# FPGA_Config.net
KiCad netlist of a schematic drawn in Altium Designer
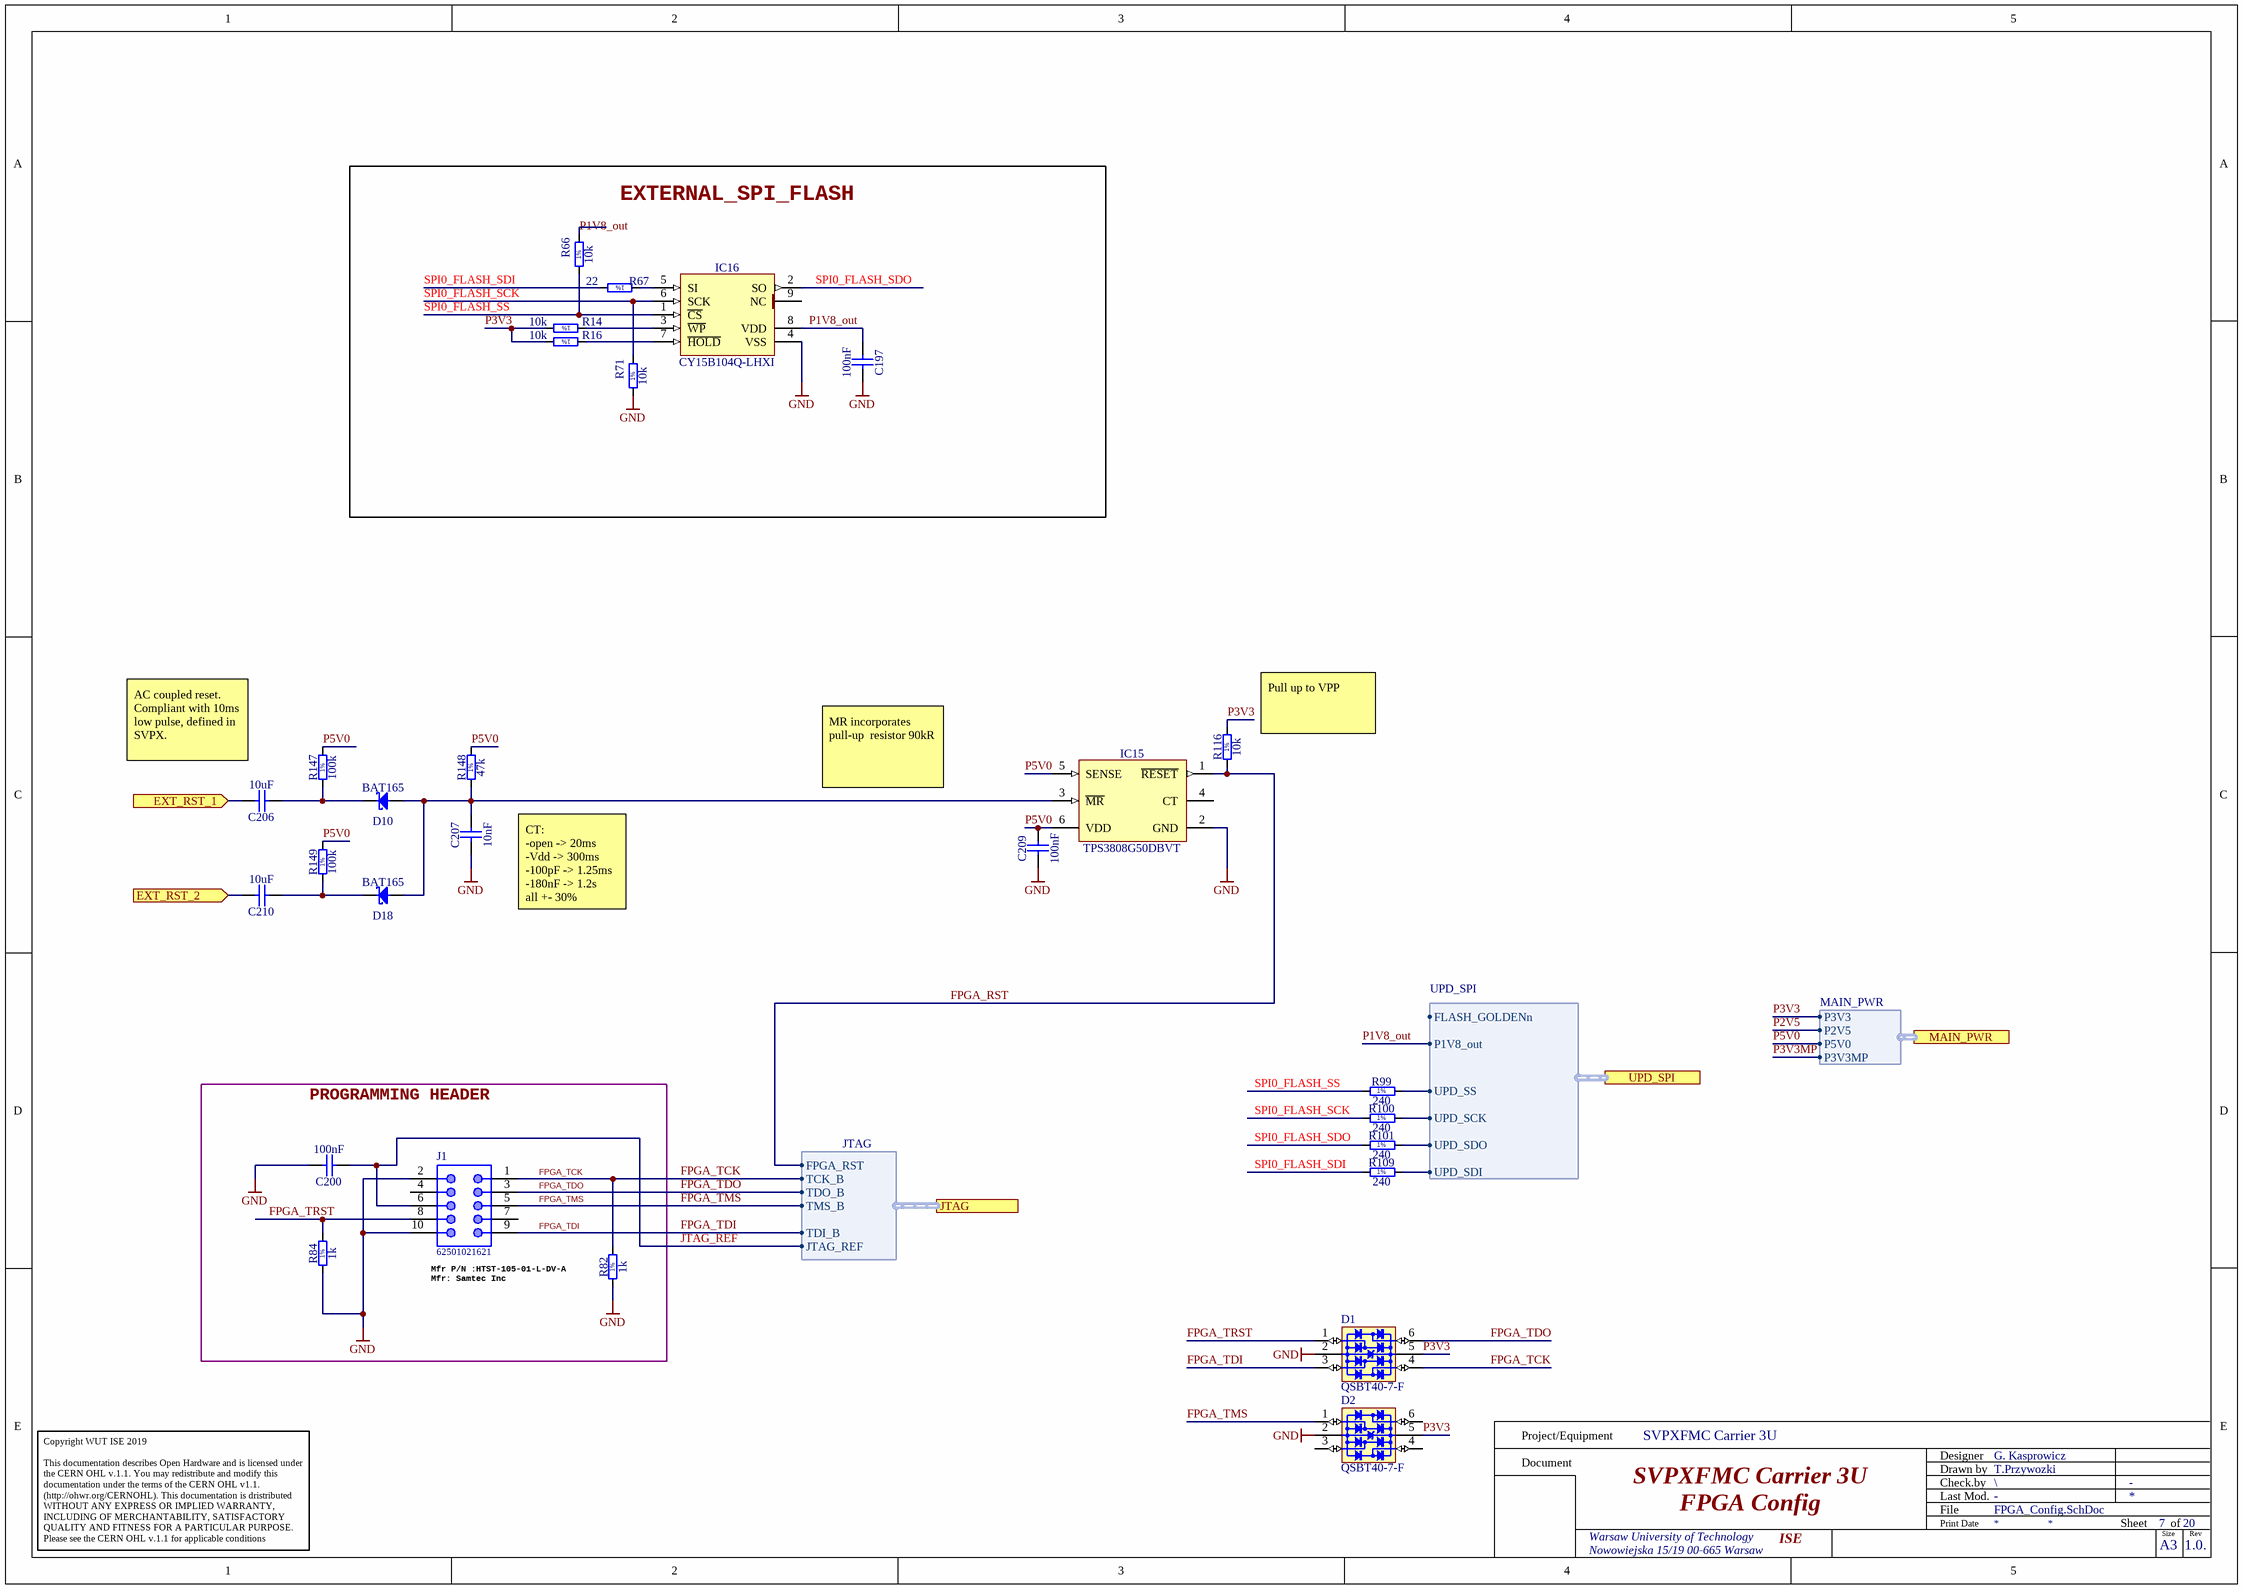
[diagram p0: FPGA_Config.SchDoc]

(export (version "E")
  (design (tool "Eeschema 10.0.6"))
  (components
    (comp (ref "C197")
      (value "100nF")
      (footprint "CAPC0603X33N")
      (description "Non-polarised capacitor")
      (fields
        (field (name "PART NUMBER") "CC0201_100NF_6.3V_10%_X5R")
        (field (name "MANUFACTURER") "GENERIC")
        (field (name "AUTHOR") "CERN DEM JLC")
      )
      (libsource (lib "Capacitors") (part "Capacitor - non polarized"))
    )
    (comp (ref "C200")
      (value "100nF")
      (footprint "CAPC0603X33N")
      (description "Non-polarised capacitor")
      (fields
        (field (name "MANUFACTURER") "GENERIC")
        (field (name "PART NUMBER") "CC0201_100NF_6.3V_10%_X5R")
        (field (name "AUTHOR") "CERN DEM JLC")
      )
      (libsource (lib "Capacitors") (part "Capacitor - non polarized"))
    )
    (comp (ref "C206")
      (value "10uF")
      (footprint "CAPC1608X80N")
      (description "Non-polarised capacitor")
      (fields
        (field (name "PART NUMBER") "CC0603_10UF_16V_20%_X5R")
        (field (name "VOLTAGE") "16V")
        (field (name "AUTHOR") "CERN DEM MR")
      )
      (libsource (lib "Capacitors") (part "Capacitor - non polarized"))
    )
    (comp (ref "C207")
      (value "10nF")
      (footprint "CAPC1005X55N")
      (description "Non-polarised capacitor")
      (fields
        (field (name "PART NUMBER") "CC0402_10NF_50V_10%_X7R")
        (field (name "VOLTAGE") "50V")
        (field (name "AUTHOR") "CERN DEM MR")
      )
      (libsource (lib "Capacitors") (part "Capacitor - non polarized"))
    )
    (comp (ref "C209")
      (value "100nF")
      (footprint "CAPC1005X55N")
      (description "Non-polarised capacitor")
      (fields
        (field (name "PART NUMBER") "CC0402_100NF_25V_10%_X7R_YUDEN_TMK105B7104KVHF")
        (field (name "VOLTAGE") "25V")
        (field (name "AUTHOR") "CERN DEM JLC")
      )
      (libsource (lib "Capacitors") (part "Capacitor - non polarized"))
    )
    (comp (ref "C210")
      (value "10uF")
      (footprint "CAPC1608X80N")
      (description "Non-polarised capacitor")
      (fields
        (field (name "PART NUMBER") "CC0603_10UF_16V_20%_X5R")
        (field (name "VOLTAGE") "16V")
        (field (name "AUTHOR") "CERN DEM MR")
      )
      (libsource (lib "Capacitors") (part "Capacitor - non polarized"))
    )
    (comp (ref "D1")
      (value "QSBT40-7-F")
      (footprint "SOT65P210X110-6N")
      (libsource (lib "LIBRARY_SCH") (part "D_TVS_QSBT40-7-F"))
    )
    (comp (ref "D2")
      (value "QSBT40-7-F")
      (footprint "SOT65P210X110-6N")
      (libsource (lib "LIBRARY_SCH") (part "D_TVS_QSBT40-7-F"))
    )
    (comp (ref "D10")
      (value "BAT165")
      (footprint "SOD2512X110N")
      (description "Schottky Diode")
      (fields
        (field (name "VOLTAGE") "40V")
        (field (name "POWER") "750mA")
        (field (name "AUTHOR") "CERN DEM JLC")
      )
      (libsource (lib "ICs And Semiconductors") (part "Diode Schottky"))
    )
    (comp (ref "D18")
      (value "BAT165")
      (footprint "SOD2512X110N")
      (description "Schottky Diode")
      (fields
        (field (name "VOLTAGE") "40V")
        (field (name "POWER") "750mA")
        (field (name "AUTHOR") "CERN DEM JLC")
      )
      (libsource (lib "ICs And Semiconductors") (part "Diode Schottky"))
    )
    (comp (ref "IC15")
      (value "TPS3808G50DBVT")
      (footprint "SOT95P280X145-6N")
      (description "Low Quiescent Current, Programmable-Delay Supervisory Circuit")
      (fields (field (name "MANUFACTURER") "TEXAS INSTRUMENTS") (field (name "AUTHOR") "CERN DEM JLC"))
      (libsource (lib "ICs And Semiconductors") (part "TPS3808xxxDBV"))
    )
    (comp (ref "IC16")
      (value "CY15B104Q-LHXI")
      (footprint "SON127P600X500X80-9N-R240X410")
      (description "4Mb Serial 3V F-RAM Memory")
      (fields (field (name "MANUFACTURER") "CYPRESS") (field (name "AUTHOR") "CERN DEM MR"))
      (libsource (lib "ICs And Semiconductors") (part "CY15B104Q"))
    )
    (comp (ref "J1")
      (value "62501021621")
      (footprint "62501021621")
      (description "Male Box Header WR-BHD with long lever, THT, Vertical, pitch 2.00 mm, 10 pins")
      (fields (field (name "PUBLISHER") "Wurth Elektronik"))
      (libsource (lib "ALTIUM-WR-BHD_BOX_HEADER_200MM_MALE-rev18b") (part "62501021621"))
    )
    (comp (ref "R14")
      (value "10k")
      (footprint "RESC1005X40N")
      (description "Resistor - 1%")
      (fields
        (field (name "MANUFACTURER PART NUMBER") "R0402_10K_1%_0.0625W_100PPM")
        (field (name "MANUFACTURER") "GENERIC")
        (field (name "AUTHOR") "CERN DEM JLC")
      )
      (libsource (lib "Resistors") (part "Resistor - 1%"))
    )
    (comp (ref "R16")
      (value "10k")
      (footprint "RESC1005X40N")
      (description "Resistor - 1%")
      (fields
        (field (name "MANUFACTURER PART NUMBER") "R0402_10K_1%_0.0625W_100PPM")
        (field (name "MANUFACTURER") "GENERIC")
        (field (name "AUTHOR") "CERN DEM JLC")
      )
      (libsource (lib "Resistors") (part "Resistor - 1%"))
    )
    (comp (ref "R66")
      (value "10k")
      (footprint "RESC1005X40N")
      (description "Resistor - 1%")
      (fields
        (field (name "MANUFACTURER PART NUMBER") "R0402_10K_1%_0.0625W_100PPM")
        (field (name "MANUFACTURER") "GENERIC")
        (field (name "AUTHOR") "CERN DEM JLC")
      )
      (libsource (lib "Resistors") (part "Resistor - 1%"))
    )
    (comp (ref "R67")
      (value "22")
      (footprint "RESC1005X40N")
      (description "Resistor - 1%")
      (fields
        (field (name "PART NUMBER") "R0402_22R_1%_0.0625W_100PPM")
        (field (name "MANUFACTURER") "GENERIC")
        (field (name "AUTHOR") "CERN DEM JLC")
      )
      (libsource (lib "Resistors") (part "Resistor - 1%"))
    )
    (comp (ref "R71")
      (value "10k")
      (footprint "RESC1005X40N")
      (description "Resistor - 1%")
      (fields
        (field (name "MANUFACTURER PART NUMBER") "R0402_10K_1%_0.0625W_100PPM")
        (field (name "MANUFACTURER") "GENERIC")
        (field (name "AUTHOR") "CERN DEM JLC")
      )
      (libsource (lib "Resistors") (part "Resistor - 1%"))
    )
    (comp (ref "R82")
      (value "1k")
      (footprint "RESC1005X40N")
      (description "Resistor - 1%")
      (fields
        (field (name "PART NUMBER") "R0402_1K_1%_0.0625W_100PPM")
        (field (name "POWER") "0.0625W")
        (field (name "AUTHOR") "CERN DEM JLC")
      )
      (libsource (lib "Resistors") (part "Resistor - 1%"))
    )
    (comp (ref "R84")
      (value "1k")
      (footprint "RESC1005X40N")
      (description "Resistor - 1%")
      (fields
        (field (name "PART NUMBER") "R0402_1K_1%_0.0625W_100PPM")
        (field (name "POWER") "0.0625W")
        (field (name "AUTHOR") "CERN DEM JLC")
      )
      (libsource (lib "Resistors") (part "Resistor - 1%"))
    )
    (comp (ref "R99")
      (value "240")
      (footprint "RESC1005X40N")
      (description "Resistor - 1%")
      (fields
        (field (name "PART NUMBER") "R0402_240R_1%_0.0625W_100PPM")
        (field (name "POWER") "0.0625W")
        (field (name "AUTHOR") "CERN DEM JLC")
      )
      (libsource (lib "Resistors") (part "Resistor - 1%"))
    )
    (comp (ref "R100")
      (value "240")
      (footprint "RESC1005X40N")
      (description "Resistor - 1%")
      (fields
        (field (name "PART NUMBER") "R0402_240R_1%_0.0625W_100PPM")
        (field (name "POWER") "0.0625W")
        (field (name "AUTHOR") "CERN DEM JLC")
      )
      (libsource (lib "Resistors") (part "Resistor - 1%"))
    )
    (comp (ref "R101")
      (value "240")
      (footprint "RESC1005X40N")
      (description "Resistor - 1%")
      (fields
        (field (name "PART NUMBER") "R0402_240R_1%_0.0625W_100PPM")
        (field (name "POWER") "0.0625W")
        (field (name "AUTHOR") "CERN DEM JLC")
      )
      (libsource (lib "Resistors") (part "Resistor - 1%"))
    )
    (comp (ref "R109")
      (value "240")
      (footprint "RESC1005X40N")
      (description "Resistor - 1%")
      (fields
        (field (name "PART NUMBER") "R0402_240R_1%_0.0625W_100PPM")
        (field (name "POWER") "0.0625W")
        (field (name "AUTHOR") "CERN DEM JLC")
      )
      (libsource (lib "Resistors") (part "Resistor - 1%"))
    )
    (comp (ref "R116")
      (value "10k")
      (footprint "RESC1005X40N")
      (description "Resistor - 1%")
      (fields
        (field (name "PART NUMBER") "R0402_10K_1%_0.0625W_100PPM")
        (field (name "POWER") "0.0625W")
        (field (name "AUTHOR") "CERN DEM JLC")
      )
      (libsource (lib "Resistors") (part "Resistor - 1%"))
    )
    (comp (ref "R147")
      (value "100k")
      (footprint "RESC1005X40N")
      (description "Resistor - 1%")
      (fields
        (field (name "PART NUMBER") "R0402_100K_1%_0.0625W_100PPM")
        (field (name "POWER") "0.0625W")
        (field (name "AUTHOR") "CERN DEM JLC")
      )
      (libsource (lib "Resistors") (part "Resistor - 1%"))
    )
    (comp (ref "R148")
      (value "47k")
      (footprint "RESC1005X40N")
      (description "Resistor - 1%")
      (fields
        (field (name "PART NUMBER") "R0402_47K_1%_0.0625W_100PPM")
        (field (name "POWER") "0.0625W")
        (field (name "AUTHOR") "CERN DEM JLC")
      )
      (libsource (lib "Resistors") (part "Resistor - 1%"))
    )
    (comp (ref "R149")
      (value "100k")
      (footprint "RESC1005X40N")
      (description "Resistor - 1%")
      (fields
        (field (name "PART NUMBER") "R0402_100K_1%_0.0625W_100PPM")
        (field (name "POWER") "0.0625W")
        (field (name "AUTHOR") "CERN DEM JLC")
      )
      (libsource (lib "Resistors") (part "Resistor - 1%"))
    )
  )
  (nets
    (net (code "4") (name "/EXT_RST_1") (class "Default")
      (node (ref "C206") (pin "2") (pinfunction "2_2") (pintype "passive"))
    )
    (net (code "5") (name "/EXT_RST_2") (class "Default")
      (node (ref "C210") (pin "2") (pinfunction "2_2") (pintype "passive"))
    )
    (net (code "6") (name "/FPGA_RST") (class "Default")
      (node (ref "IC15") (pin "1") (pinfunction "~{RESET}_1") (pintype "output"))
      (node (ref "R116") (pin "1") (pinfunction "1_1") (pintype "passive"))
    )
    (net (code "7") (name "/FPGA_TCK") (class "Default")
      (node (ref "D1") (pin "4") (pinfunction "I/O3_4") (pintype "bidirectional"))
      (node (ref "J1") (pin "1") (pinfunction "1_1") (pintype "passive"))
      (node (ref "R82") (pin "2") (pinfunction "2_2") (pintype "passive"))
    )
    (net (code "8") (name "/FPGA_TDI") (class "Default")
      (node (ref "D1") (pin "3") (pinfunction "I/O2_3") (pintype "bidirectional"))
      (node (ref "J1") (pin "9") (pinfunction "9_9") (pintype "passive"))
    )
    (net (code "9") (name "/FPGA_TDO") (class "Default")
      (node (ref "D1") (pin "6") (pinfunction "I/O4_6") (pintype "bidirectional"))
      (node (ref "J1") (pin "3") (pinfunction "3_3") (pintype "passive"))
    )
    (net (code "10") (name "/FPGA_TMS") (class "Default")
      (node (ref "D2") (pin "1") (pinfunction "I/O1_1") (pintype "bidirectional"))
      (node (ref "J1") (pin "5") (pinfunction "5_5") (pintype "passive"))
    )
    (net (code "11") (name "/FPGA_TRST") (class "Default")
      (node (ref "D1") (pin "1") (pinfunction "I/O1_1") (pintype "bidirectional"))
      (node (ref "J1") (pin "8") (pinfunction "8_8") (pintype "passive"))
      (node (ref "R84") (pin "2") (pinfunction "2_2") (pintype "passive"))
    )
    (net (code "12") (name "/JTAG_REF") (class "Default")
      (node (ref "C200") (pin "1") (pinfunction "1_1") (pintype "passive"))
      (node (ref "J1") (pin "6") (pinfunction "6_6") (pintype "passive"))
    )
    (net (code "13") (name "/P1V8_out") (class "Default")
      (node (ref "C197") (pin "2") (pinfunction "2_2") (pintype "passive"))
      (node (ref "IC16") (pin "8") (pinfunction "VDD_8") (pintype "power_in"))
      (node (ref "R66") (pin "2") (pinfunction "2_2") (pintype "passive"))
    )
    (net (code "15") (name "/P3V3") (class "Default")
      (node (ref "D1") (pin "5") (pinfunction "VBUS_5") (pintype "power_in"))
      (node (ref "D2") (pin "5") (pinfunction "VBUS_5") (pintype "power_in"))
      (node (ref "R116") (pin "2") (pinfunction "2_2") (pintype "passive"))
      (node (ref "R14") (pin "2") (pinfunction "2_2") (pintype "passive"))
      (node (ref "R16") (pin "2") (pinfunction "2_2") (pintype "passive"))
    )
    (net (code "17") (name "/P5V0") (class "Default")
      (node (ref "C209") (pin "2") (pinfunction "2_2") (pintype "passive"))
      (node (ref "IC15") (pin "5") (pinfunction "SENSE_5") (pintype "input"))
      (node (ref "IC15") (pin "6") (pinfunction "VDD_6") (pintype "power_in"))
      (node (ref "R147") (pin "2") (pinfunction "2_2") (pintype "passive"))
      (node (ref "R148") (pin "2") (pinfunction "2_2") (pintype "passive"))
      (node (ref "R149") (pin "2") (pinfunction "2_2") (pintype "passive"))
    )
    (net (code "18") (name "/SPI0_FLASH_SCK") (class "Default")
      (node (ref "IC16") (pin "6") (pinfunction "SCK_6") (pintype "input"))
      (node (ref "R100") (pin "1") (pinfunction "1_1") (pintype "passive"))
      (node (ref "R71") (pin "2") (pinfunction "2_2") (pintype "passive"))
    )
    (net (code "19") (name "/SPI0_FLASH_SDI") (class "Default")
      (node (ref "R109") (pin "1") (pinfunction "1_1") (pintype "passive"))
      (node (ref "R67") (pin "2") (pinfunction "2_2") (pintype "passive"))
    )
    (net (code "20") (name "/SPI0_FLASH_SDO") (class "Default")
      (node (ref "IC16") (pin "2") (pinfunction "SO_2") (pintype "output"))
      (node (ref "R101") (pin "1") (pinfunction "1_1") (pintype "passive"))
    )
    (net (code "21") (name "/SPI0_FLASH_SS") (class "Default")
      (node (ref "IC16") (pin "1") (pinfunction "~{CS}_1") (pintype "input"))
      (node (ref "R66") (pin "1") (pinfunction "1_1") (pintype "passive"))
      (node (ref "R99") (pin "1") (pinfunction "1_1") (pintype "passive"))
    )
    (net (code "22") (name "/UPD_SCK") (class "Default")
      (node (ref "R100") (pin "2") (pinfunction "2_2") (pintype "passive"))
    )
    (net (code "23") (name "/UPD_SDI") (class "Default")
      (node (ref "R109") (pin "2") (pinfunction "2_2") (pintype "passive"))
    )
    (net (code "24") (name "/UPD_SDO") (class "Default")
      (node (ref "R101") (pin "2") (pinfunction "2_2") (pintype "passive"))
    )
    (net (code "25") (name "/UPD_SS") (class "Default")
      (node (ref "R99") (pin "2") (pinfunction "2_2") (pintype "passive"))
    )
    (net (code "29") (name "GND") (class "Default")
      (node (ref "C197") (pin "1") (pinfunction "1_1") (pintype "passive"))
      (node (ref "C200") (pin "2") (pinfunction "2_2") (pintype "passive"))
      (node (ref "C207") (pin "1") (pinfunction "1_1") (pintype "passive"))
      (node (ref "C209") (pin "1") (pinfunction "1_1") (pintype "passive"))
      (node (ref "D1") (pin "2") (pinfunction "GND_2") (pintype "power_in"))
      (node (ref "D2") (pin "2") (pinfunction "GND_2") (pintype "power_in"))
      (node (ref "IC15") (pin "2") (pinfunction "GND_2") (pintype "power_in"))
      (node (ref "IC16") (pin "4") (pinfunction "VSS_4") (pintype "power_in"))
      (node (ref "J1") (pin "10") (pinfunction "10_10") (pintype "passive"))
      (node (ref "J1") (pin "2") (pinfunction "2_2") (pintype "passive"))
      (node (ref "R71") (pin "1") (pinfunction "1_1") (pintype "passive"))
      (node (ref "R82") (pin "1") (pinfunction "1_1") (pintype "passive"))
      (node (ref "R84") (pin "1") (pinfunction "1_1") (pintype "passive"))
    )
    (net (code "30") (name "Net-(D10-A)") (class "Default")
      (node (ref "C207") (pin "2") (pinfunction "2_2") (pintype "passive"))
      (node (ref "D10") (pin "2") (pinfunction "A_2") (pintype "passive"))
      (node (ref "D18") (pin "2") (pinfunction "A_2") (pintype "passive"))
      (node (ref "IC15") (pin "3") (pinfunction "~{MR}_3") (pintype "input"))
      (node (ref "R148") (pin "1") (pinfunction "1_1") (pintype "passive"))
    )
    (net (code "31") (name "Net-(D10-C)") (class "Default")
      (node (ref "C206") (pin "1") (pinfunction "1_1") (pintype "passive"))
      (node (ref "D10") (pin "1") (pinfunction "C_1") (pintype "passive"))
      (node (ref "R147") (pin "1") (pinfunction "1_1") (pintype "passive"))
    )
    (net (code "32") (name "Net-(D18-C)") (class "Default")
      (node (ref "C210") (pin "1") (pinfunction "1_1") (pintype "passive"))
      (node (ref "D18") (pin "1") (pinfunction "C_1") (pintype "passive"))
      (node (ref "R149") (pin "1") (pinfunction "1_1") (pintype "passive"))
    )
    (net (code "33") (name "Net-(IC16-SI)") (class "Default")
      (node (ref "IC16") (pin "5") (pinfunction "SI_5") (pintype "input"))
      (node (ref "R67") (pin "1") (pinfunction "1_1") (pintype "passive"))
    )
    (net (code "34") (name "Net-(IC16-~{HOLD})") (class "Default")
      (node (ref "IC16") (pin "7") (pinfunction "~{HOLD}_7") (pintype "input"))
      (node (ref "R16") (pin "1") (pinfunction "1_1") (pintype "passive"))
    )
    (net (code "35") (name "Net-(IC16-~{WP})") (class "Default")
      (node (ref "IC16") (pin "3") (pinfunction "~{WP}_3") (pintype "input"))
      (node (ref "R14") (pin "1") (pinfunction "1_1") (pintype "passive"))
    )
    (net (code "36") (name "unconnected-(D2-I{slash}O2-Pad3)") (class "Default")
      (node (ref "D2") (pin "3") (pinfunction "I/O2_3") (pintype "bidirectional"))
    )
    (net (code "37") (name "unconnected-(D2-I{slash}O3-Pad4)") (class "Default")
      (node (ref "D2") (pin "4") (pinfunction "I/O3_4") (pintype "bidirectional"))
    )
    (net (code "38") (name "unconnected-(D2-I{slash}O4-Pad6)") (class "Default")
      (node (ref "D2") (pin "6") (pinfunction "I/O4_6") (pintype "bidirectional"))
    )
    (net (code "39") (name "unconnected-(IC15-CT-Pad4)") (class "Default")
      (node (ref "IC15") (pin "4") (pinfunction "CT_4") (pintype "passive"))
    )
    (net (code "40") (name "unconnected-(IC16-NC-Pad9)") (class "Default")
      (node (ref "IC16") (pin "9") (pinfunction "NC_9") (pintype "power_in"))
    )
    (net (code "41") (name "unconnected-(J1-Pad4)") (class "Default")
      (node (ref "J1") (pin "4") (pinfunction "4_4") (pintype "passive"))
    )
    (net (code "42") (name "unconnected-(J1-Pad7)") (class "Default")
      (node (ref "J1") (pin "7") (pinfunction "7_7") (pintype "passive"))
    )
  )
)
